# RF_2.net
KiCad netlist of a schematic drawn in Altium Designer
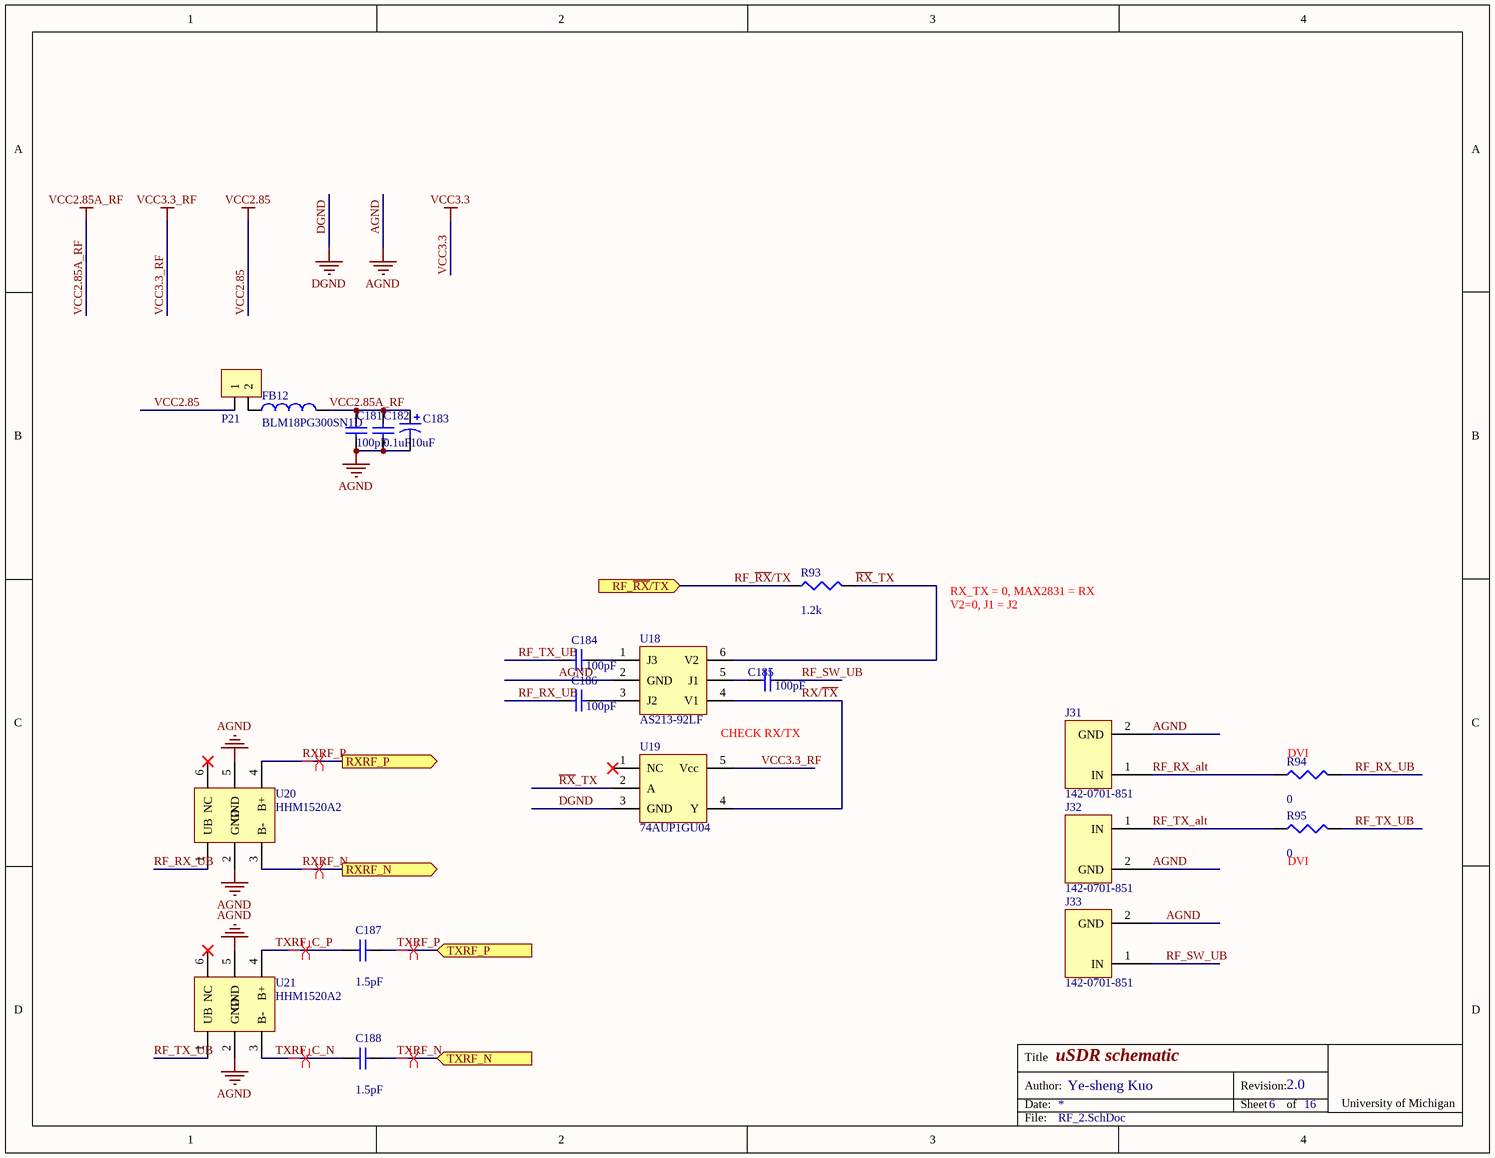
[diagram p0: RF_2.SchDoc]

(export (version "E")
  (design (tool "Eeschema 10.0.6"))
  (components
    (comp (ref "C181")
      (value "100pF")
      (footprint "0402")
      (description "Capacitor (Semiconductor SIM Model)")
      (fields (field (name "PUBLISHER") "Altium Limited"))
      (libsource (lib "Miscellaneous Devices") (part "Cap Semi"))
    )
    (comp (ref "C182")
      (value "0.1uF")
      (footprint "0402")
      (description "Capacitor (Semiconductor SIM Model)")
      (fields (field (name "PUBLISHER") "Altium Limited"))
      (libsource (lib "Miscellaneous Devices") (part "Cap Semi"))
    )
    (comp (ref "C183")
      (value "10uF")
      (footprint "C0805")
      (description "Polarized Capacitor (Surface Mount)")
      (fields (field (name "PUBLISHER") "Altium Limited"))
      (libsource (lib "Miscellaneous Devices") (part "Cap Pol3"))
    )
    (comp (ref "C184")
      (value "100pF")
      (footprint "0402")
      (description "Capacitor (Semiconductor SIM Model)")
      (fields (field (name "PUBLISHER") "Altium Limited"))
      (libsource (lib "Miscellaneous Devices") (part "Cap Semi"))
    )
    (comp (ref "C185")
      (value "100pF")
      (footprint "0402")
      (description "Capacitor (Semiconductor SIM Model)")
      (fields (field (name "PUBLISHER") "Altium Limited"))
      (libsource (lib "Miscellaneous Devices") (part "Cap Semi"))
    )
    (comp (ref "C186")
      (value "100pF")
      (footprint "0402")
      (description "Capacitor (Semiconductor SIM Model)")
      (fields (field (name "PUBLISHER") "Altium Limited"))
      (libsource (lib "Miscellaneous Devices") (part "Cap Semi"))
    )
    (comp (ref "C187")
      (value "1.5pF")
      (footprint "0402")
      (description "Capacitor (Semiconductor SIM Model)")
      (fields (field (name "PUBLISHER") "Altium Limited"))
      (libsource (lib "Miscellaneous Devices") (part "Cap Semi"))
    )
    (comp (ref "C188")
      (value "1.5pF")
      (footprint "0402")
      (description "Capacitor (Semiconductor SIM Model)")
      (fields (field (name "PUBLISHER") "Altium Limited"))
      (libsource (lib "Miscellaneous Devices") (part "Cap Semi"))
    )
    (comp (ref "FB12")
      (value "BLM18PG300SN1D")
      (footprint "1608[0603]")
      (description "FERRITE CHIP 30 OHM 1000MA 0603")
      (libsource (lib "SDR") (part "Ferrite Bead"))
    )
    (comp (ref "J31")
      (value "142-0701-851")
      (footprint "SMA_SMD")
      (description "CONN JACK END LAUNCH PC GOLD SMA")
      (libsource (lib "") (part "SMA_connector_1"))
    )
    (comp (ref "J32")
      (value "142-0701-851")
      (footprint "SMA_SMD")
      (description "CONN JACK END LAUNCH PC GOLD SMA")
      (libsource (lib "SDR") (part "SMA_connector"))
    )
    (comp (ref "J33")
      (value "142-0701-851")
      (footprint "SMA_SMD")
      (description "CONN JACK END LAUNCH PC GOLD SMA")
      (libsource (lib "") (part "SMA_connector_1"))
    )
    (comp (ref "P21")
      (value "1 x 2 header")
      (footprint "1x2 header")
      (description "100 mils standard header")
      (libsource (lib "SDR") (part "1 x 2 header"))
    )
    (comp (ref "R93")
      (value "1.2k")
      (footprint "0402")
      (description "Resistor")
      (fields (field (name "Comment") "1.2K") (field (name "PUBLISHER") "Altium Limited"))
      (libsource (lib "Miscellaneous Devices") (part "Res3"))
    )
    (comp (ref "R94")
      (value "0")
      (footprint "0402")
      (description "Resistor")
      (fields (field (name "PUBLISHER") "Altium Limited"))
      (libsource (lib "Miscellaneous Devices") (part "Res3"))
    )
    (comp (ref "R95")
      (value "0")
      (footprint "0402")
      (description "Resistor")
      (fields (field (name "PUBLISHER") "Altium Limited"))
      (libsource (lib "Miscellaneous Devices") (part "Res3"))
    )
    (comp (ref "U18")
      (value "AS213-92LF")
      (footprint "SOT363-6N")
      (description "IC SW SPDT 0.1-3GHZ GAAS SC88")
      (libsource (lib "SDR") (part "AS213-92LF"))
    )
    (comp (ref "U19")
      (value "74AUP1GU04")
      (footprint "SOT353-5N")
      (description "IC UNBUFFERED INVERTER LP 5TSSOP")
      (libsource (lib "SDR") (part "74AUP1GU04"))
    )
    (comp (ref "U20")
      (value "HHM1520A2")
      (footprint "HHM1520A2")
      (description "XFRMR BALUN RF 2.4GHZ SMD")
      (libsource (lib "SDR") (part "TDK chip Balun"))
    )
    (comp (ref "U21")
      (value "HHM1520A2")
      (footprint "HHM1520A2")
      (description "XFRMR BALUN RF 2.4GHZ SMD")
      (libsource (lib "SDR") (part "TDK chip Balun"))
    )
  )
  (nets
    (net (code "1") (name "/RF_RX_UB") (class "Default")
      (node (ref "C186") (pin "2") (pinfunction "2_2") (pintype "passive"))
      (node (ref "R94") (pin "2") (pinfunction "2_2") (pintype "passive"))
      (node (ref "U20") (pin "1") (pinfunction "UB_1") (pintype "passive"))
    )
    (net (code "2") (name "/RF_RX_alt") (class "Default")
      (node (ref "J31") (pin "1") (pinfunction "IN_1") (pintype "passive"))
      (node (ref "R94") (pin "1") (pinfunction "1_1") (pintype "passive"))
    )
    (net (code "3") (name "/RF_SW_UB") (class "Default")
      (node (ref "C185") (pin "1") (pinfunction "1_1") (pintype "passive"))
      (node (ref "J33") (pin "1") (pinfunction "IN_1") (pintype "passive"))
    )
    (net (code "4") (name "/RF_TX_UB") (class "Default")
      (node (ref "C184") (pin "2") (pinfunction "2_2") (pintype "passive"))
      (node (ref "R95") (pin "2") (pinfunction "2_2") (pintype "passive"))
      (node (ref "U21") (pin "1") (pinfunction "UB_1") (pintype "passive"))
    )
    (net (code "5") (name "/RF_TX_alt") (class "Default")
      (node (ref "J32") (pin "1") (pinfunction "IN_1") (pintype "passive"))
      (node (ref "R95") (pin "1") (pinfunction "1_1") (pintype "passive"))
    )
    (net (code "6") (name "/RF_~{RX}{slash}TX") (class "Default")
      (node (ref "R93") (pin "1") (pinfunction "1_1") (pintype "passive"))
    )
    (net (code "7") (name "/RXRF_N") (class "Default")
      (node (ref "U20") (pin "3") (pinfunction "B-_3") (pintype "passive"))
    )
    (net (code "8") (name "/RXRF_P") (class "Default")
      (node (ref "U20") (pin "4") (pinfunction "B+_4") (pintype "passive"))
    )
    (net (code "9") (name "/RX{slash}~{TX}") (class "Default")
      (node (ref "U18") (pin "4") (pinfunction "V1_4") (pintype "passive"))
      (node (ref "U19") (pin "4") (pinfunction "Y_4") (pintype "passive"))
    )
    (net (code "10") (name "/TXRF_C_N") (class "Default")
      (node (ref "C188") (pin "2") (pinfunction "2_2") (pintype "passive"))
      (node (ref "U21") (pin "3") (pinfunction "B-_3") (pintype "passive"))
    )
    (net (code "11") (name "/TXRF_C_P") (class "Default")
      (node (ref "C187") (pin "2") (pinfunction "2_2") (pintype "passive"))
      (node (ref "U21") (pin "4") (pinfunction "B+_4") (pintype "passive"))
    )
    (net (code "12") (name "/TXRF_N") (class "Default")
      (node (ref "C188") (pin "1") (pinfunction "1_1") (pintype "passive"))
    )
    (net (code "13") (name "/TXRF_P") (class "Default")
      (node (ref "C187") (pin "1") (pinfunction "1_1") (pintype "passive"))
    )
    (net (code "14") (name "/~{RX}_TX") (class "Default")
      (node (ref "R93") (pin "2") (pinfunction "2_2") (pintype "passive"))
      (node (ref "U18") (pin "6") (pinfunction "V2_6") (pintype "passive"))
      (node (ref "U19") (pin "2") (pinfunction "A_2") (pintype "passive"))
    )
    (net (code "15") (name "AGND") (class "Default")
      (node (ref "C181") (pin "1") (pinfunction "1_1") (pintype "passive"))
      (node (ref "C182") (pin "1") (pinfunction "1_1") (pintype "passive"))
      (node (ref "C183") (pin "2") (pinfunction "2_2") (pintype "passive"))
      (node (ref "J31") (pin "2") (pinfunction "GND_2") (pintype "passive"))
      (node (ref "J32") (pin "2") (pinfunction "GND_2") (pintype "passive"))
      (node (ref "J33") (pin "2") (pinfunction "GND_2") (pintype "passive"))
      (node (ref "U18") (pin "2") (pinfunction "GND_2") (pintype "passive"))
      (node (ref "U20") (pin "2") (pinfunction "GND_2") (pintype "passive"))
      (node (ref "U20") (pin "5") (pinfunction "GND_5") (pintype "passive"))
      (node (ref "U21") (pin "2") (pinfunction "GND_2") (pintype "passive"))
      (node (ref "U21") (pin "5") (pinfunction "GND_5") (pintype "passive"))
    )
    (net (code "16") (name "DGND") (class "Default")
      (node (ref "U19") (pin "3") (pinfunction "GND_3") (pintype "passive"))
    )
    (net (code "17") (name "Net-(FB12-Pad1)") (class "Default")
      (node (ref "FB12") (pin "1") (pinfunction "1_1") (pintype "passive"))
      (node (ref "P21") (pin "2") (pinfunction "2_2") (pintype "passive"))
    )
    (net (code "18") (name "Net-(U18-J1)") (class "Default")
      (node (ref "C185") (pin "2") (pinfunction "2_2") (pintype "passive"))
      (node (ref "U18") (pin "5") (pinfunction "J1_5") (pintype "passive"))
    )
    (net (code "19") (name "Net-(U18-J2)") (class "Default")
      (node (ref "C186") (pin "1") (pinfunction "1_1") (pintype "passive"))
      (node (ref "U18") (pin "3") (pinfunction "J2_3") (pintype "passive"))
    )
    (net (code "20") (name "Net-(U18-J3)") (class "Default")
      (node (ref "C184") (pin "1") (pinfunction "1_1") (pintype "passive"))
      (node (ref "U18") (pin "1") (pinfunction "J3_1") (pintype "passive"))
    )
    (net (code "21") (name "VCC2.85") (class "Default")
      (node (ref "P21") (pin "1") (pinfunction "1_1") (pintype "passive"))
    )
    (net (code "22") (name "VCC2.85A_RF") (class "Default")
      (node (ref "C181") (pin "2") (pinfunction "2_2") (pintype "passive"))
      (node (ref "C182") (pin "2") (pinfunction "2_2") (pintype "passive"))
      (node (ref "C183") (pin "1") (pinfunction "1_1") (pintype "passive"))
      (node (ref "FB12") (pin "2") (pinfunction "2_2") (pintype "passive"))
    )
    (net (code "24") (name "VCC3.3_RF") (class "Default")
      (node (ref "U19") (pin "5") (pinfunction "Vcc_5") (pintype "passive"))
    )
    (net (code "25") (name "unconnected-(U19-NC-Pad1)") (class "Default")
      (node (ref "U19") (pin "1") (pinfunction "NC_1") (pintype "passive+no_connect"))
    )
    (net (code "26") (name "unconnected-(U20-NC-Pad6)") (class "Default")
      (node (ref "U20") (pin "6") (pinfunction "NC_6") (pintype "passive+no_connect"))
    )
    (net (code "27") (name "unconnected-(U21-NC-Pad6)") (class "Default")
      (node (ref "U21") (pin "6") (pinfunction "NC_6") (pintype "passive+no_connect"))
    )
  )
)
